# GPS.net
KiCad netlist of a schematic drawn in Altium Designer
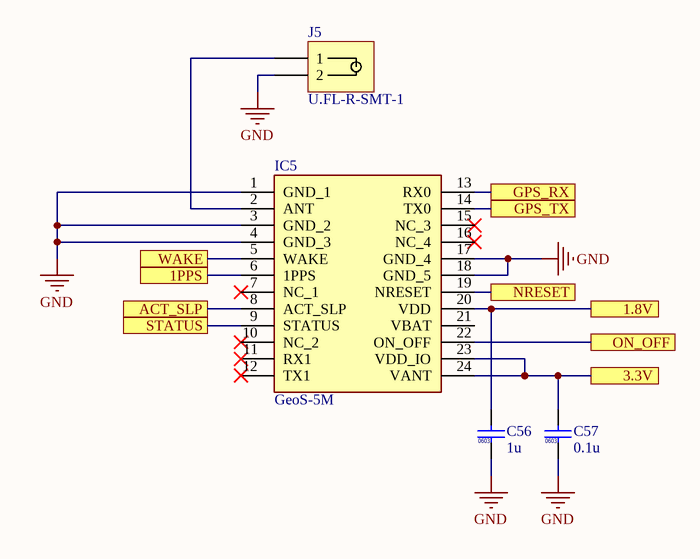
[diagram p0: GPS.SchDoc]

(export (version "E")
  (design (tool "Eeschema 10.0.6"))
  (components
    (comp (ref "C56")
      (value "1u")
      (footprint "CAPC1608-0603L")
      (description "Capacitor 0603")
      (fields (field (name "Comment") "CAPC_0603"))
      (libsource (lib "Passive") (part "CAPC_0603"))
    )
    (comp (ref "C57")
      (value "0.1u")
      (footprint "CAPC1608-0603L")
      (description "Capacitor 0603")
      (fields (field (name "Comment") "CAPC_0603"))
      (libsource (lib "Passive") (part "CAPC_0603"))
    )
    (comp (ref "IC5")
      (value "GeoS-5M")
      (footprint "Bogdanov:GeoS5M")
      (description "Integrated Circuit")
      (libsource (lib "Bogdanov") (part "GeoS-5M"))
    )
    (comp (ref "J5")
      (value "U.FL-R-SMT-1")
      (footprint "HIROSE_U.FL-R-SMT-1(10)")
      (description "Hirose U.FL-R-SMT-1 HF connector")
      (libsource (lib "Connectors") (part "U.FL-R-SMT-1"))
    )
  )
  (nets
    (net (code "1") (name "/1.8V") (class "Default")
      (node (ref "C56") (pin "2") (pinfunction "2_2") (pintype "passive"))
      (node (ref "IC5") (pin "20") (pinfunction "VDD_20") (pintype "passive"))
    )
    (net (code "2") (name "/1PPS") (class "Default")
      (node (ref "IC5") (pin "6") (pinfunction "1PPS_6") (pintype "passive"))
    )
    (net (code "3") (name "/3.3V") (class "Default")
      (node (ref "C57") (pin "2") (pinfunction "2_2") (pintype "passive"))
      (node (ref "IC5") (pin "23") (pinfunction "VDD_IO_23") (pintype "passive"))
      (node (ref "IC5") (pin "24") (pinfunction "VANT_24") (pintype "passive"))
    )
    (net (code "4") (name "/ACT_SLP") (class "Default")
      (node (ref "IC5") (pin "8") (pinfunction "ACT_SLP_8") (pintype "passive"))
    )
    (net (code "5") (name "/GPS_RX") (class "Default")
      (node (ref "IC5") (pin "13") (pinfunction "RX0_13") (pintype "passive"))
    )
    (net (code "6") (name "/GPS_TX") (class "Default")
      (node (ref "IC5") (pin "14") (pinfunction "TX0_14") (pintype "passive"))
    )
    (net (code "7") (name "/NRESET") (class "Default")
      (node (ref "IC5") (pin "19") (pinfunction "NRESET_19") (pintype "passive"))
    )
    (net (code "8") (name "/ON_OFF") (class "Default")
      (node (ref "IC5") (pin "22") (pinfunction "ON_OFF_22") (pintype "passive"))
    )
    (net (code "9") (name "/STATUS") (class "Default")
      (node (ref "IC5") (pin "9") (pinfunction "STATUS_9") (pintype "passive"))
    )
    (net (code "10") (name "/WAKE") (class "Default")
      (node (ref "IC5") (pin "5") (pinfunction "WAKE_5") (pintype "passive"))
    )
    (net (code "11") (name "GND") (class "Default")
      (node (ref "C56") (pin "1") (pinfunction "1_1") (pintype "passive"))
      (node (ref "C57") (pin "1") (pinfunction "1_1") (pintype "passive"))
      (node (ref "IC5") (pin "1") (pinfunction "GND_1_1") (pintype "passive"))
      (node (ref "IC5") (pin "17") (pinfunction "GND_4_17") (pintype "passive"))
      (node (ref "IC5") (pin "18") (pinfunction "GND_5_18") (pintype "passive"))
      (node (ref "IC5") (pin "3") (pinfunction "GND_2_3") (pintype "passive"))
      (node (ref "IC5") (pin "4") (pinfunction "GND_3_4") (pintype "passive"))
      (node (ref "J5") (pin "2") (pinfunction "2_2") (pintype "passive"))
    )
    (net (code "12") (name "Net-(IC5-ANT)") (class "Default")
      (node (ref "IC5") (pin "2") (pinfunction "ANT_2") (pintype "passive"))
      (node (ref "J5") (pin "1") (pinfunction "1_1") (pintype "passive"))
    )
    (net (code "13") (name "unconnected-(IC5-NC_1-Pad7)") (class "Default")
      (node (ref "IC5") (pin "7") (pinfunction "NC_1_7") (pintype "passive+no_connect"))
    )
    (net (code "14") (name "unconnected-(IC5-NC_2-Pad10)") (class "Default")
      (node (ref "IC5") (pin "10") (pinfunction "NC_2_10") (pintype "passive+no_connect"))
    )
    (net (code "15") (name "unconnected-(IC5-NC_3-Pad15)") (class "Default")
      (node (ref "IC5") (pin "15") (pinfunction "NC_3_15") (pintype "passive+no_connect"))
    )
    (net (code "16") (name "unconnected-(IC5-NC_4-Pad16)") (class "Default")
      (node (ref "IC5") (pin "16") (pinfunction "NC_4_16") (pintype "passive+no_connect"))
    )
    (net (code "17") (name "unconnected-(IC5-RX1-Pad11)") (class "Default")
      (node (ref "IC5") (pin "11") (pinfunction "RX1_11") (pintype "passive+no_connect"))
    )
    (net (code "18") (name "unconnected-(IC5-TX1-Pad12)") (class "Default")
      (node (ref "IC5") (pin "12") (pinfunction "TX1_12") (pintype "passive+no_connect"))
    )
    (net (code "19") (name "unconnected-(IC5-VBAT-Pad21)") (class "Default")
      (node (ref "IC5") (pin "21") (pinfunction "VBAT_21") (pintype "passive"))
    )
  )
)
